# Weather_Shield.net
KiCad netlist of a schematic drawn in EAGLE
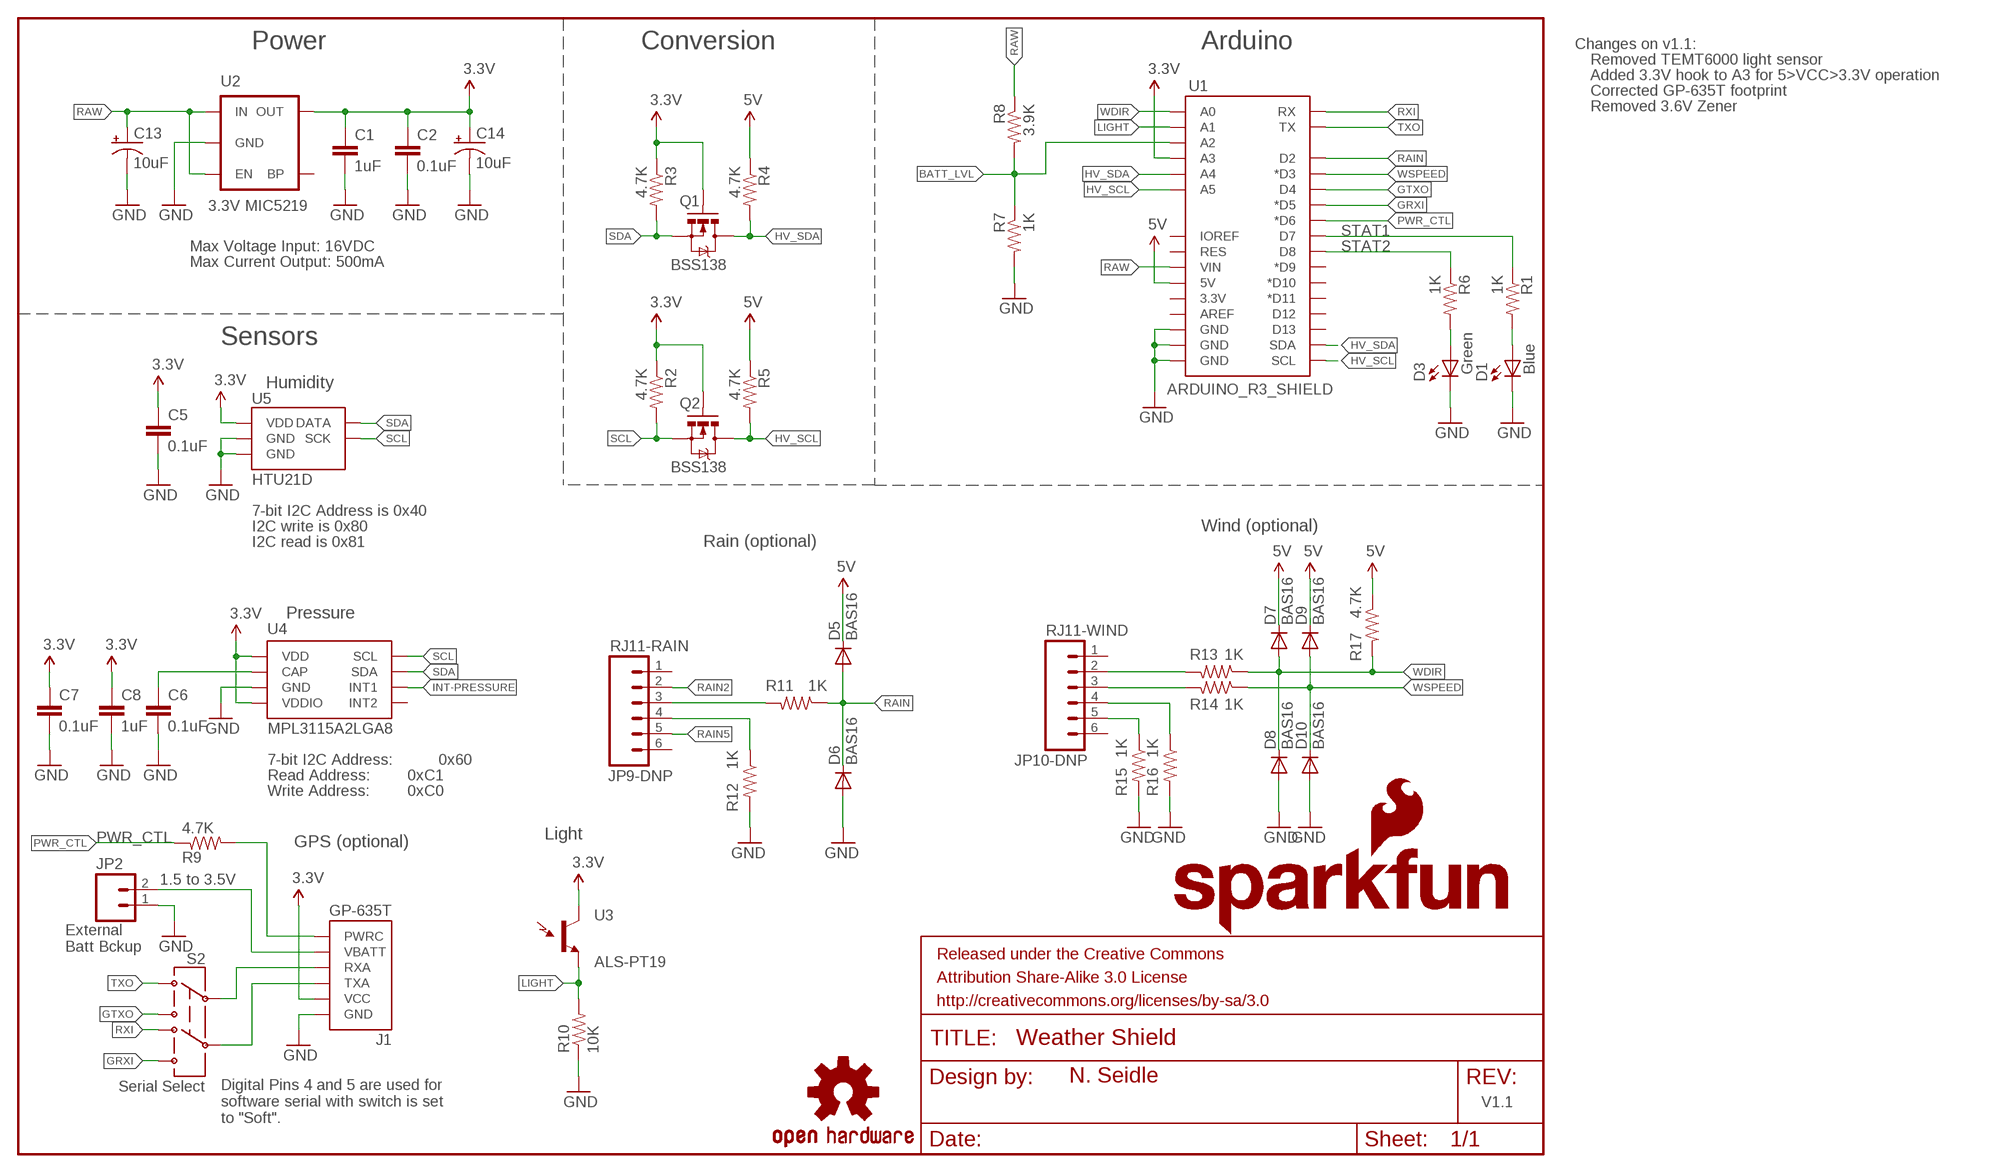
[diagram p0: schematic, sheet 1]

(export (version "E")
  (design (tool "Eeschema 10.0.6"))
  (components
    (comp (ref "C1")
      (value "1uF")
      (footprint "eagle-import:0603-CAP")
      (libsource (lib "eagle-import") (part "CAP0603-CAP"))
    )
    (comp (ref "C2")
      (value "0.1uF")
      (footprint "eagle-import:0603-CAP")
      (libsource (lib "eagle-import") (part "CAP0603-CAP"))
    )
    (comp (ref "C5")
      (value "0.1uF")
      (footprint "eagle-import:0603-CAP")
      (libsource (lib "eagle-import") (part "CAP0603-CAP"))
    )
    (comp (ref "C6")
      (value "0.1uF")
      (footprint "eagle-import:0603-CAP")
      (libsource (lib "eagle-import") (part "CAP0603-CAP"))
    )
    (comp (ref "C7")
      (value "0.1uF")
      (footprint "eagle-import:0603-CAP")
      (libsource (lib "eagle-import") (part "CAP0603-CAP"))
    )
    (comp (ref "C8")
      (value "1uF")
      (footprint "eagle-import:0603-CAP")
      (libsource (lib "eagle-import") (part "CAP0603-CAP"))
    )
    (comp (ref "C13")
      (value "10uF")
      (footprint "eagle-import:EIA3216")
      (libsource (lib "eagle-import") (part "CAP_POL1206"))
    )
    (comp (ref "C14")
      (value "10uF")
      (footprint "eagle-import:EIA3216")
      (libsource (lib "eagle-import") (part "CAP_POL1206"))
    )
    (comp (ref "D1")
      (value "Blue")
      (footprint "eagle-import:LED-0603")
      (libsource (lib "eagle-import") (part "LED0603"))
    )
    (comp (ref "D3")
      (value "Green")
      (footprint "eagle-import:LED-0603")
      (libsource (lib "eagle-import") (part "LED0603"))
    )
    (comp (ref "D5")
      (value "BAS16")
      (footprint "eagle-import:SOD-323")
      (libsource (lib "eagle-import") (part "DIODESOD"))
    )
    (comp (ref "D6")
      (value "BAS16")
      (footprint "eagle-import:SOD-323")
      (libsource (lib "eagle-import") (part "DIODESOD"))
    )
    (comp (ref "D7")
      (value "BAS16")
      (footprint "eagle-import:SOD-323")
      (libsource (lib "eagle-import") (part "DIODESOD"))
    )
    (comp (ref "D8")
      (value "BAS16")
      (footprint "eagle-import:SOD-323")
      (libsource (lib "eagle-import") (part "DIODESOD"))
    )
    (comp (ref "D9")
      (value "BAS16")
      (footprint "eagle-import:SOD-323")
      (libsource (lib "eagle-import") (part "DIODESOD"))
    )
    (comp (ref "D10")
      (value "BAS16")
      (footprint "eagle-import:SOD-323")
      (libsource (lib "eagle-import") (part "DIODESOD"))
    )
    (comp (ref "FRAME1")
      (value "FRAME-LETTER")
      (footprint "eagle-import:CREATIVE_COMMONS")
      (libsource (lib "eagle-import") (part "FRAME-LETTER"))
    )
    (comp (ref "J1")
      (value "GP-635T")
      (footprint "eagle-import:GP-635T")
      (libsource (lib "eagle-import") (part "GP-635TSMD"))
    )
    (comp (ref "JP2")
      (value "External Batt Bckup")
      (footprint "eagle-import:1X02")
      (libsource (lib "eagle-import") (part "M02PTH"))
    )
    (comp (ref "JP9-DNP")
      (value "RJ11-RAIN")
      (footprint "eagle-import:RJ11-6")
      (libsource (lib "eagle-import") (part "RJ11-6PTH"))
    )
    (comp (ref "JP10-DNP")
      (value "RJ11-WIND")
      (footprint "eagle-import:RJ11-6")
      (libsource (lib "eagle-import") (part "RJ11-6PTH"))
    )
    (comp (ref "LOGO1")
      (value "OSHW-LOGOM")
      (footprint "eagle-import:OSHW-LOGO-M")
      (libsource (lib "eagle-import") (part "OSHW-LOGOM"))
    )
    (comp (ref "LOGO2")
      (value "SFE_LOGO_NAME_FLAME.1_INCH")
      (footprint "eagle-import:SFE_LOGO_NAME_FLAME_.1")
      (libsource (lib "eagle-import") (part "SFE_LOGO_NAME_FLAME.1_INCH"))
    )
    (comp (ref "Q1")
      (value "BSS138")
      (footprint "eagle-import:SOT23-3")
      (libsource (lib "eagle-import") (part "MOSFET-NCHANNELSMD"))
    )
    (comp (ref "Q2")
      (value "BSS138")
      (footprint "eagle-import:SOT23-3")
      (libsource (lib "eagle-import") (part "MOSFET-NCHANNELSMD"))
    )
    (comp (ref "R1")
      (value "1K")
      (footprint "eagle-import:0603-RES")
      (libsource (lib "eagle-import") (part "RESISTOR0603-RES"))
    )
    (comp (ref "R2")
      (value "4.7K")
      (footprint "eagle-import:0603-RES")
      (libsource (lib "eagle-import") (part "RESISTOR0603-RES"))
    )
    (comp (ref "R3")
      (value "4.7K")
      (footprint "eagle-import:0603-RES")
      (libsource (lib "eagle-import") (part "RESISTOR0603-RES"))
    )
    (comp (ref "R4")
      (value "4.7K")
      (footprint "eagle-import:0603-RES")
      (libsource (lib "eagle-import") (part "RESISTOR0603-RES"))
    )
    (comp (ref "R5")
      (value "4.7K")
      (footprint "eagle-import:0603-RES")
      (libsource (lib "eagle-import") (part "RESISTOR0603-RES"))
    )
    (comp (ref "R6")
      (value "1K")
      (footprint "eagle-import:0603-RES")
      (libsource (lib "eagle-import") (part "RESISTOR0603-RES"))
    )
    (comp (ref "R7")
      (value "1K")
      (footprint "eagle-import:0603-RES")
      (libsource (lib "eagle-import") (part "RESISTOR0603-RES"))
    )
    (comp (ref "R8")
      (value "3.9K")
      (footprint "eagle-import:0603-RES")
      (libsource (lib "eagle-import") (part "RESISTOR0603-RES"))
    )
    (comp (ref "R9")
      (value "4.7K")
      (footprint "eagle-import:0603-RES")
      (libsource (lib "eagle-import") (part "RESISTOR0603-RES"))
    )
    (comp (ref "R10")
      (value "10K")
      (footprint "eagle-import:0603-RES")
      (libsource (lib "eagle-import") (part "SparkFun-Passives_RESISTOR0603-RES"))
    )
    (comp (ref "R11")
      (value "1K")
      (footprint "eagle-import:0603-RES")
      (libsource (lib "eagle-import") (part "RESISTOR0603-RES"))
    )
    (comp (ref "R12")
      (value "1K")
      (footprint "eagle-import:0603-RES")
      (libsource (lib "eagle-import") (part "RESISTOR0603-RES"))
    )
    (comp (ref "R13")
      (value "1K")
      (footprint "eagle-import:0603-RES")
      (libsource (lib "eagle-import") (part "RESISTOR0603-RES"))
    )
    (comp (ref "R14")
      (value "1K")
      (footprint "eagle-import:0603-RES")
      (libsource (lib "eagle-import") (part "RESISTOR0603-RES"))
    )
    (comp (ref "R15")
      (value "1K")
      (footprint "eagle-import:0603-RES")
      (libsource (lib "eagle-import") (part "RESISTOR0603-RES"))
    )
    (comp (ref "R16")
      (value "1K")
      (footprint "eagle-import:0603-RES")
      (libsource (lib "eagle-import") (part "RESISTOR0603-RES"))
    )
    (comp (ref "R17")
      (value "4.7K")
      (footprint "eagle-import:0603-RES")
      (libsource (lib "eagle-import") (part "RESISTOR0603-RES"))
    )
    (comp (ref "S2")
      (value "Serial Select")
      (footprint "eagle-import:AYZ0202")
      (libsource (lib "eagle-import") (part "SWITCH-DPDTAYZ0202"))
    )
    (comp (ref "U1")
      (value "ARDUINO_R3_SHIELD")
      (footprint "eagle-import:UNO_R3_SHIELD")
      (libsource (lib "eagle-import") (part "ARDUINO_R3_SHIELD"))
    )
    (comp (ref "U2")
      (value "3.3V MIC5219")
      (footprint "eagle-import:SOT23-5")
      (libsource (lib "eagle-import") (part "V_REG_LDOSMD"))
    )
    (comp (ref "U3")
      (value "ALS-PT19")
      (footprint "eagle-import:ALS-PT19")
      (libsource (lib "eagle-import") (part "LIGHTSENSORALS"))
    )
    (comp (ref "U4")
      (value "MPL3115A2LGA8")
      (footprint "eagle-import:LGA8")
      (libsource (lib "eagle-import") (part "MPL3115A2LGA8"))
    )
    (comp (ref "U5")
      (value "HTU21D")
      (footprint "eagle-import:HTU21D")
      (libsource (lib "eagle-import") (part "HTU21DSMD"))
    )
  )
  (nets
    (net (code "1") (name "/STAT1") (class "Default")
      (node (ref "R1") (pin "1") (pinfunction "1_1") (pintype "passive"))
      (node (ref "U1") (pin "D7") (pinfunction "D7_D7") (pintype "bidirectional"))
    )
    (net (code "2") (name "/STAT2") (class "Default")
      (node (ref "R6") (pin "1") (pinfunction "1_1") (pintype "passive"))
      (node (ref "U1") (pin "D8") (pinfunction "D8_D8") (pintype "bidirectional"))
    )
    (net (code "3") (name "3.3V") (class "Default")
      (node (ref "C1") (pin "1") (pinfunction "1_1") (pintype "passive"))
      (node (ref "C14") (pin "A") (pinfunction "+_A") (pintype "passive"))
      (node (ref "C2") (pin "1") (pinfunction "1_1") (pintype "passive"))
      (node (ref "C5") (pin "1") (pinfunction "1_1") (pintype "passive"))
      (node (ref "C7") (pin "1") (pinfunction "1_1") (pintype "passive"))
      (node (ref "C8") (pin "1") (pinfunction "1_1") (pintype "passive"))
      (node (ref "J1") (pin "2") (pinfunction "VCC_2") (pintype "power_in"))
      (node (ref "Q1") (pin "1") (pinfunction "G_1") (pintype "passive"))
      (node (ref "Q2") (pin "1") (pinfunction "G_1") (pintype "passive"))
      (node (ref "R2") (pin "1") (pinfunction "1_1") (pintype "passive"))
      (node (ref "R3") (pin "1") (pinfunction "1_1") (pintype "passive"))
      (node (ref "U1") (pin "A3") (pinfunction "A3_A3") (pintype "bidirectional"))
      (node (ref "U2") (pin "5") (pinfunction "OUT_5") (pintype "passive"))
      (node (ref "U3") (pin "C") (pinfunction "C1_C") (pintype "passive"))
      (node (ref "U4") (pin "1") (pinfunction "VDD_1") (pintype "power_in"))
      (node (ref "U4") (pin "4") (pinfunction "VDDIO_4") (pintype "power_in"))
      (node (ref "U5") (pin "VDD") (pinfunction "VDD_VDD") (pintype "power_in"))
    )
    (net (code "4") (name "5V") (class "Default")
      (node (ref "D5") (pin "1") (pinfunction "C_1") (pintype "passive"))
      (node (ref "D7") (pin "1") (pinfunction "C_1") (pintype "passive"))
      (node (ref "D9") (pin "1") (pinfunction "C_1") (pintype "passive"))
      (node (ref "R17") (pin "1") (pinfunction "1_1") (pintype "passive"))
      (node (ref "R4") (pin "1") (pinfunction "1_1") (pintype "passive"))
      (node (ref "R5") (pin "1") (pinfunction "1_1") (pintype "passive"))
      (node (ref "U1") (pin "5V") (pinfunction "5V_5V") (pintype "bidirectional"))
    )
    (net (code "5") (name "BATT_LVL") (class "Default")
      (node (ref "R7") (pin "1") (pinfunction "1_1") (pintype "passive"))
      (node (ref "R8") (pin "2") (pinfunction "2_2") (pintype "passive"))
      (node (ref "U1") (pin "A2") (pinfunction "A2_A2") (pintype "bidirectional"))
    )
    (net (code "6") (name "GND") (class "Default")
      (node (ref "C1") (pin "2") (pinfunction "2_2") (pintype "passive"))
      (node (ref "C13") (pin "C") (pinfunction "-_C") (pintype "passive"))
      (node (ref "C14") (pin "C") (pinfunction "-_C") (pintype "passive"))
      (node (ref "C2") (pin "2") (pinfunction "2_2") (pintype "passive"))
      (node (ref "C5") (pin "2") (pinfunction "2_2") (pintype "passive"))
      (node (ref "C6") (pin "2") (pinfunction "2_2") (pintype "passive"))
      (node (ref "C7") (pin "2") (pinfunction "2_2") (pintype "passive"))
      (node (ref "C8") (pin "2") (pinfunction "2_2") (pintype "passive"))
      (node (ref "D1") (pin "C") (pinfunction "C_C") (pintype "passive"))
      (node (ref "D10") (pin "2") (pinfunction "A_2") (pintype "passive"))
      (node (ref "D3") (pin "C") (pinfunction "C_C") (pintype "passive"))
      (node (ref "D6") (pin "2") (pinfunction "A_2") (pintype "passive"))
      (node (ref "D8") (pin "2") (pinfunction "A_2") (pintype "passive"))
      (node (ref "J1") (pin "1") (pinfunction "GND_1") (pintype "power_in"))
      (node (ref "JP2") (pin "1") (pinfunction "1_1") (pintype "passive"))
      (node (ref "R10") (pin "1") (pinfunction "1_1") (pintype "passive"))
      (node (ref "R12") (pin "2") (pinfunction "2_2") (pintype "passive"))
      (node (ref "R15") (pin "2") (pinfunction "2_2") (pintype "passive"))
      (node (ref "R16") (pin "2") (pinfunction "2_2") (pintype "passive"))
      (node (ref "R7") (pin "2") (pinfunction "2_2") (pintype "passive"))
      (node (ref "U1") (pin "GND@0") (pinfunction "GND_GND@0") (pintype "bidirectional"))
      (node (ref "U1") (pin "GND@1") (pinfunction "GND_GND@1") (pintype "bidirectional"))
      (node (ref "U1") (pin "GND@2") (pinfunction "GND_GND@2") (pintype "bidirectional"))
      (node (ref "U2") (pin "2") (pinfunction "GND_2") (pintype "input"))
      (node (ref "U4") (pin "3") (pinfunction "GND_3") (pintype "power_in"))
      (node (ref "U5") (pin "7") (pinfunction "GND_7") (pintype "power_in"))
      (node (ref "U5") (pin "GND") (pinfunction "GND_GND") (pintype "power_in"))
    )
    (net (code "7") (name "GRXI") (class "Default")
      (node (ref "S2") (pin "6") (pinfunction "6_6") (pintype "bidirectional"))
      (node (ref "U1") (pin "D5") (pinfunction "*D5_D5") (pintype "bidirectional"))
    )
    (net (code "8") (name "GTXO") (class "Default")
      (node (ref "S2") (pin "3") (pinfunction "3_3") (pintype "bidirectional"))
      (node (ref "U1") (pin "D4") (pinfunction "D4_D4") (pintype "bidirectional"))
    )
    (net (code "9") (name "HV_SCL") (class "Default")
      (node (ref "Q2") (pin "3") (pinfunction "D_3") (pintype "passive"))
      (node (ref "R5") (pin "2") (pinfunction "2_2") (pintype "passive"))
      (node (ref "U1") (pin "A5") (pinfunction "A5_A5") (pintype "bidirectional"))
      (node (ref "U1") (pin "SCL") (pinfunction "SCL_SCL") (pintype "bidirectional"))
    )
    (net (code "10") (name "HV_SDA") (class "Default")
      (node (ref "Q1") (pin "3") (pinfunction "D_3") (pintype "passive"))
      (node (ref "R4") (pin "2") (pinfunction "2_2") (pintype "passive"))
      (node (ref "U1") (pin "A4") (pinfunction "A4_A4") (pintype "bidirectional"))
      (node (ref "U1") (pin "SDA") (pinfunction "SDA_SDA") (pintype "bidirectional"))
    )
    (net (code "11") (name "INT-PRESSURE") (class "Default")
      (node (ref "U4") (pin "6") (pinfunction "INT1_6") (pintype "output"))
    )
    (net (code "12") (name "LIGHT") (class "Default")
      (node (ref "R10") (pin "2") (pinfunction "2_2") (pintype "passive"))
      (node (ref "U1") (pin "A1") (pinfunction "A1_A1") (pintype "bidirectional"))
      (node (ref "U3") (pin "E") (pinfunction "E1_E") (pintype "passive"))
    )
    (net (code "13") (name "Net-(D1-PadA)") (class "Default")
      (node (ref "D1") (pin "A") (pinfunction "A_A") (pintype "passive"))
      (node (ref "R1") (pin "2") (pinfunction "2_2") (pintype "passive"))
    )
    (net (code "14") (name "Net-(D3-PadA)") (class "Default")
      (node (ref "D3") (pin "A") (pinfunction "A_A") (pintype "passive"))
      (node (ref "R6") (pin "2") (pinfunction "2_2") (pintype "passive"))
    )
    (net (code "15") (name "Net-(J1-PWRC)") (class "Default")
      (node (ref "J1") (pin "6") (pinfunction "PWRC_6") (pintype "input"))
      (node (ref "R9") (pin "2") (pinfunction "2_2") (pintype "passive"))
    )
    (net (code "16") (name "Net-(J1-RXA)") (class "Default")
      (node (ref "J1") (pin "4") (pinfunction "RXA_4") (pintype "input"))
      (node (ref "S2") (pin "2") (pinfunction "2_2") (pintype "bidirectional"))
    )
    (net (code "17") (name "Net-(J1-TXA)") (class "Default")
      (node (ref "J1") (pin "3") (pinfunction "TXA_3") (pintype "output"))
      (node (ref "S2") (pin "5") (pinfunction "5_5") (pintype "bidirectional"))
    )
    (net (code "18") (name "Net-(J1-VBATT)") (class "Default")
      (node (ref "J1") (pin "5") (pinfunction "VBATT_5") (pintype "power_in"))
      (node (ref "JP2") (pin "2") (pinfunction "2_2") (pintype "passive"))
    )
    (net (code "19") (name "Net-(JP9-DNP-Pad3)") (class "Default")
      (node (ref "JP9-DNP") (pin "3") (pinfunction "3_3") (pintype "passive"))
      (node (ref "R11") (pin "2") (pinfunction "2_2") (pintype "passive"))
    )
    (net (code "20") (name "Net-(JP9-DNP-Pad4)") (class "Default")
      (node (ref "JP9-DNP") (pin "4") (pinfunction "4_4") (pintype "passive"))
      (node (ref "R12") (pin "1") (pinfunction "1_1") (pintype "passive"))
    )
    (net (code "21") (name "Net-(JP10-DNP-Pad2)") (class "Default")
      (node (ref "JP10-DNP") (pin "2") (pinfunction "2_2") (pintype "passive"))
      (node (ref "R13") (pin "2") (pinfunction "2_2") (pintype "passive"))
    )
    (net (code "22") (name "Net-(JP10-DNP-Pad3)") (class "Default")
      (node (ref "JP10-DNP") (pin "3") (pinfunction "3_3") (pintype "passive"))
      (node (ref "R14") (pin "2") (pinfunction "2_2") (pintype "passive"))
    )
    (net (code "23") (name "Net-(JP10-DNP-Pad4)") (class "Default")
      (node (ref "JP10-DNP") (pin "4") (pinfunction "4_4") (pintype "passive"))
      (node (ref "R16") (pin "1") (pinfunction "1_1") (pintype "passive"))
    )
    (net (code "24") (name "Net-(JP10-DNP-Pad5)") (class "Default")
      (node (ref "JP10-DNP") (pin "5") (pinfunction "5_5") (pintype "passive"))
      (node (ref "R15") (pin "1") (pinfunction "1_1") (pintype "passive"))
    )
    (net (code "25") (name "Net-(U4-CAP)") (class "Default")
      (node (ref "C6") (pin "1") (pinfunction "1_1") (pintype "passive"))
      (node (ref "U4") (pin "2") (pinfunction "CAP_2") (pintype "power_in"))
    )
    (net (code "26") (name "PWR_CTL") (class "Default")
      (node (ref "R9") (pin "1") (pinfunction "1_1") (pintype "passive"))
      (node (ref "U1") (pin "D6") (pinfunction "*D6_D6") (pintype "bidirectional"))
    )
    (net (code "27") (name "RAIN") (class "Default")
      (node (ref "D5") (pin "2") (pinfunction "A_2") (pintype "passive"))
      (node (ref "D6") (pin "1") (pinfunction "C_1") (pintype "passive"))
      (node (ref "R11") (pin "1") (pinfunction "1_1") (pintype "passive"))
      (node (ref "U1") (pin "D2") (pinfunction "D2_D2") (pintype "bidirectional"))
    )
    (net (code "28") (name "RAIN2") (class "Default")
      (node (ref "JP9-DNP") (pin "2") (pinfunction "2_2") (pintype "passive"))
    )
    (net (code "29") (name "RAIN5") (class "Default")
      (node (ref "JP9-DNP") (pin "5") (pinfunction "5_5") (pintype "passive"))
    )
    (net (code "30") (name "RAW") (class "Default")
      (node (ref "C13") (pin "A") (pinfunction "+_A") (pintype "passive"))
      (node (ref "R8") (pin "1") (pinfunction "1_1") (pintype "passive"))
      (node (ref "U1") (pin "VIN") (pinfunction "VIN_VIN") (pintype "bidirectional"))
      (node (ref "U2") (pin "1") (pinfunction "IN_1") (pintype "input"))
      (node (ref "U2") (pin "3") (pinfunction "EN_3") (pintype "input"))
    )
    (net (code "31") (name "RXI") (class "Default")
      (node (ref "S2") (pin "4") (pinfunction "4_4") (pintype "bidirectional"))
      (node (ref "U1") (pin "RX") (pinfunction "RX_RX") (pintype "bidirectional"))
    )
    (net (code "32") (name "SCL") (class "Default")
      (node (ref "Q2") (pin "2") (pinfunction "S_2") (pintype "passive"))
      (node (ref "R2") (pin "2") (pinfunction "2_2") (pintype "passive"))
      (node (ref "U4") (pin "8") (pinfunction "SCL_8") (pintype "bidirectional"))
      (node (ref "U5") (pin "SCK") (pinfunction "SCK_SCK") (pintype "input"))
    )
    (net (code "33") (name "SDA") (class "Default")
      (node (ref "Q1") (pin "2") (pinfunction "S_2") (pintype "passive"))
      (node (ref "R3") (pin "2") (pinfunction "2_2") (pintype "passive"))
      (node (ref "U4") (pin "7") (pinfunction "SDA_7") (pintype "bidirectional"))
      (node (ref "U5") (pin "DATA") (pinfunction "DATA_DATA") (pintype "bidirectional"))
    )
    (net (code "34") (name "TXO") (class "Default")
      (node (ref "S2") (pin "1") (pinfunction "1_1") (pintype "bidirectional"))
      (node (ref "U1") (pin "TX") (pinfunction "TX_TX") (pintype "bidirectional"))
    )
    (net (code "35") (name "WDIR") (class "Default")
      (node (ref "D7") (pin "2") (pinfunction "A_2") (pintype "passive"))
      (node (ref "D8") (pin "1") (pinfunction "C_1") (pintype "passive"))
      (node (ref "R13") (pin "1") (pinfunction "1_1") (pintype "passive"))
      (node (ref "R17") (pin "2") (pinfunction "2_2") (pintype "passive"))
      (node (ref "U1") (pin "A0") (pinfunction "A0_A0") (pintype "bidirectional"))
    )
    (net (code "36") (name "WSPEED") (class "Default")
      (node (ref "D10") (pin "1") (pinfunction "C_1") (pintype "passive"))
      (node (ref "D9") (pin "2") (pinfunction "A_2") (pintype "passive"))
      (node (ref "R14") (pin "1") (pinfunction "1_1") (pintype "passive"))
      (node (ref "U1") (pin "D3") (pinfunction "*D3_D3") (pintype "bidirectional"))
    )
    (net (code "37") (name "unconnected-(JP9-DNP-Pad1)") (class "Default")
      (node (ref "JP9-DNP") (pin "1") (pinfunction "1_1") (pintype "passive"))
    )
    (net (code "38") (name "unconnected-(JP9-DNP-Pad6)") (class "Default")
      (node (ref "JP9-DNP") (pin "6") (pinfunction "6_6") (pintype "passive"))
    )
    (net (code "39") (name "unconnected-(JP10-DNP-Pad1)") (class "Default")
      (node (ref "JP10-DNP") (pin "1") (pinfunction "1_1") (pintype "passive"))
    )
    (net (code "40") (name "unconnected-(JP10-DNP-Pad6)") (class "Default")
      (node (ref "JP10-DNP") (pin "6") (pinfunction "6_6") (pintype "passive"))
    )
    (net (code "41") (name "unconnected-(U1-*D9-PadD9)") (class "Default")
      (node (ref "U1") (pin "D9") (pinfunction "*D9_D9") (pintype "bidirectional"))
    )
    (net (code "42") (name "unconnected-(U1-*D10-PadD10)") (class "Default")
      (node (ref "U1") (pin "D10") (pinfunction "*D10_D10") (pintype "bidirectional"))
    )
    (net (code "43") (name "unconnected-(U1-*D11-PadD11)") (class "Default")
      (node (ref "U1") (pin "D11") (pinfunction "*D11_D11") (pintype "bidirectional"))
    )
    (net (code "44") (name "unconnected-(U1-Pad3.3V)") (class "Default")
      (node (ref "U1") (pin "3.3V") (pinfunction "3.3V_3.3V") (pintype "bidirectional"))
    )
    (net (code "45") (name "unconnected-(U1-PadAREF)") (class "Default")
      (node (ref "U1") (pin "AREF") (pinfunction "AREF_AREF") (pintype "bidirectional"))
    )
    (net (code "46") (name "unconnected-(U1-PadD12)") (class "Default")
      (node (ref "U1") (pin "D12") (pinfunction "D12_D12") (pintype "bidirectional"))
    )
    (net (code "47") (name "unconnected-(U1-PadD13)") (class "Default")
      (node (ref "U1") (pin "D13") (pinfunction "D13_D13") (pintype "bidirectional"))
    )
    (net (code "48") (name "unconnected-(U1-PadIOREF)") (class "Default")
      (node (ref "U1") (pin "IOREF") (pinfunction "IOREF_IOREF") (pintype "bidirectional"))
    )
    (net (code "49") (name "unconnected-(U1-PadRES)") (class "Default")
      (node (ref "U1") (pin "RES") (pinfunction "RES_RES") (pintype "bidirectional"))
    )
    (net (code "50") (name "unconnected-(U2-BP-Pad4)") (class "Default")
      (node (ref "U2") (pin "4") (pinfunction "BP_4") (pintype "input"))
    )
    (net (code "51") (name "unconnected-(U4-INT2-Pad5)") (class "Default")
      (node (ref "U4") (pin "5") (pinfunction "INT2_5") (pintype "output"))
    )
  )
)
